# charger_1A.net
KiCad netlist of a schematic drawn in Altium Designer
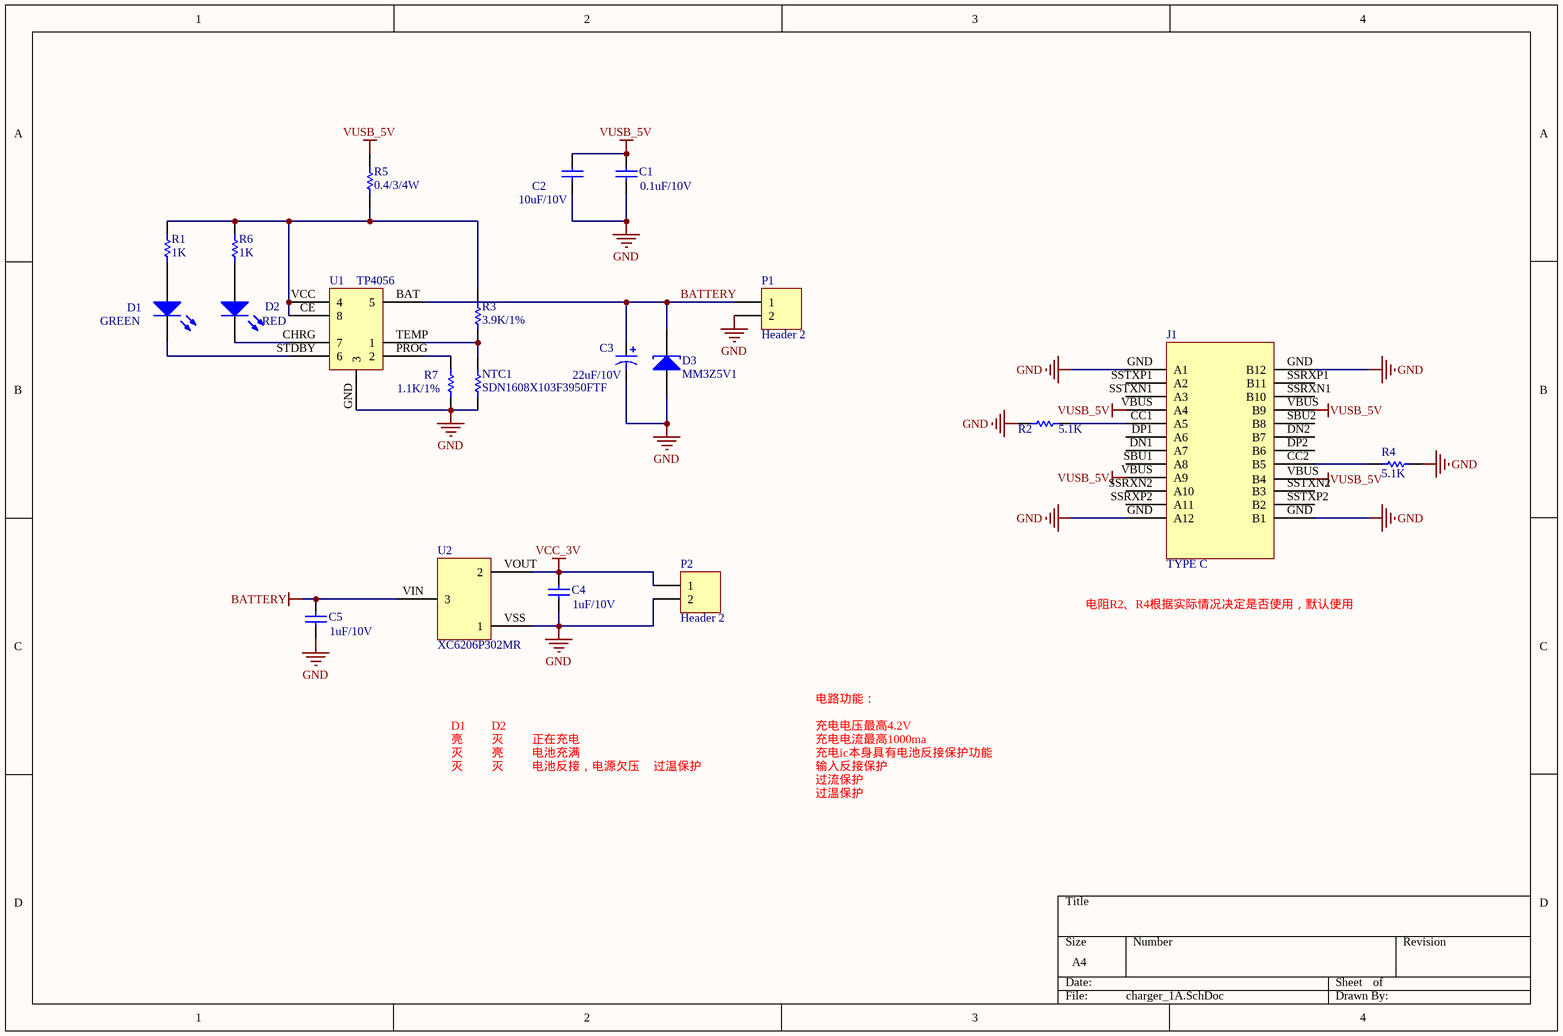
[diagram p0: charger_1A.SchDoc]

(export (version "E")
  (design (tool "Eeschema 10.0.6"))
  (components
    (comp (ref "C1")
      (value "0.1uF/10V")
      (footprint "0603C")
      (description "Capacitor")
      (fields (field (name "PUBLISHER") "Altium Limited"))
      (libsource (lib "Miscellaneous Devices") (part "Cap"))
    )
    (comp (ref "C2")
      (value "10uF/10V")
      (footprint "0603C")
      (description "Capacitor")
      (fields (field (name "PUBLISHER") "Altium Limited"))
      (libsource (lib "Miscellaneous Devices") (part "Cap"))
    )
    (comp (ref "C3")
      (value "22uF/10V")
      (footprint "1210E")
      (description "Polarized Capacitor (Radial)")
      (fields (field (name "PUBLISHER") "Altium Limited"))
      (libsource (lib "Miscellaneous Devices") (part "Cap Pol1"))
    )
    (comp (ref "C4")
      (value "1uF/10V")
      (footprint "0603C")
      (description "Capacitor")
      (fields (field (name "PUBLISHER") "Altium Limited"))
      (libsource (lib "Miscellaneous Devices") (part "Cap"))
    )
    (comp (ref "C5")
      (value "1uF/10V")
      (footprint "0603C")
      (description "Capacitor")
      (fields (field (name "PUBLISHER") "Altium Limited"))
      (libsource (lib "Miscellaneous Devices") (part "Cap"))
    )
    (comp (ref "D1")
      (value "~")
      (footprint "0603LED")
      (description "Typical INFRARED GaAs LED")
      (fields (field (name "PUBLISHER") "GREEN"))
      (libsource (lib "Miscellaneous Devices") (part "LED0"))
    )
    (comp (ref "D2")
      (value "~")
      (footprint "0603LED")
      (description "Typical INFRARED GaAs LED")
      (fields (field (name "PUBLISHER") "RED"))
      (libsource (lib "Miscellaneous Devices") (part "LED0"))
    )
    (comp (ref "D3")
      (value "MM3Z5V1")
      (footprint "SOD323")
      (description "Tunnel Diode - RLC Model")
      (fields (field (name "PUBLISHER") "Altium Limited"))
      (libsource (lib "Miscellaneous Devices") (part "D Tunnel1"))
    )
    (comp (ref "J1") (value "TYPE C") (libsource (lib "CHARGER") (part "TYPE C")))
    (comp (ref "NTC1")
      (value "SDN1608X103F3950FTF")
      (footprint "0603R")
      (description "Semiconductor Resistor")
      (fields (field (name "PUBLISHER") "Altium Limited"))
      (libsource (lib "Miscellaneous Devices") (part "Res Semi"))
    )
    (comp (ref "P1")
      (value "Header 2")
      (footprint "HDR1X2")
      (description "Header, 2-Pin")
      (fields (field (name "PUBLISHER") "Altium Limited"))
      (libsource (lib "Miscellaneous Connectors") (part "Header 2"))
    )
    (comp (ref "P2")
      (value "Header 2")
      (footprint "HDR1X2")
      (description "Header, 2-Pin")
      (fields (field (name "PUBLISHER") "Altium Limited"))
      (libsource (lib "Miscellaneous Connectors") (part "Header 2"))
    )
    (comp (ref "R1")
      (value "1K")
      (footprint "0603R")
      (description "Semiconductor Resistor")
      (fields (field (name "PUBLISHER") "Altium Limited"))
      (libsource (lib "Miscellaneous Devices") (part "Res Semi"))
    )
    (comp (ref "R2")
      (value "5.1K")
      (footprint "0603R")
      (description "Semiconductor Resistor")
      (fields (field (name "PUBLISHER") "Altium Limited"))
      (libsource (lib "Miscellaneous Devices") (part "Res Semi"))
    )
    (comp (ref "R3")
      (value "3.9K/1%")
      (footprint "0603R")
      (description "Semiconductor Resistor")
      (fields (field (name "PUBLISHER") "Altium Limited"))
      (libsource (lib "Miscellaneous Devices") (part "Res Semi"))
    )
    (comp (ref "R4")
      (value "5.1K")
      (footprint "0603R")
      (description "Semiconductor Resistor")
      (fields (field (name "PUBLISHER") "Altium Limited"))
      (libsource (lib "Miscellaneous Devices") (part "Res Semi"))
    )
    (comp (ref "R5")
      (value "0.4/3/4W")
      (footprint "0603R")
      (description "Semiconductor Resistor")
      (fields (field (name "PUBLISHER") "Altium Limited"))
      (libsource (lib "Miscellaneous Devices") (part "Res Semi"))
    )
    (comp (ref "R6")
      (value "1K")
      (footprint "0603R")
      (description "Semiconductor Resistor")
      (fields (field (name "PUBLISHER") "Altium Limited"))
      (libsource (lib "Miscellaneous Devices") (part "Res Semi"))
    )
    (comp (ref "R7")
      (value "1.1K/1%")
      (footprint "0603R")
      (description "Semiconductor Resistor")
      (fields (field (name "PUBLISHER") "Altium Limited"))
      (libsource (lib "Miscellaneous Devices") (part "Res Semi"))
    )
    (comp (ref "U1") (value "TP4056") (libsource (lib "CHARGER") (part "TP4056")))
    (comp (ref "U2") (value "XC6206P302MR") (libsource (lib "CHARGER") (part "XC6206P302MR")))
  )
  (nets
    (net (code "1") (name "BATTERY") (class "Default")
      (node (ref "C3") (pin "1") (pinfunction "1_1") (pintype "passive"))
      (node (ref "C5") (pin "2") (pinfunction "2_2") (pintype "passive"))
      (node (ref "D3") (pin "2") (pinfunction "K_2") (pintype "passive"))
      (node (ref "P1") (pin "1") (pinfunction "1_1") (pintype "passive"))
      (node (ref "U1") (pin "BAT") (pinfunction "5_BAT") (pintype "passive"))
      (node (ref "U2") (pin "VIN") (pinfunction "3_VIN") (pintype "passive"))
    )
    (net (code "2") (name "GND") (class "Default")
      (node (ref "C1") (pin "1") (pinfunction "1_1") (pintype "passive"))
      (node (ref "C2") (pin "1") (pinfunction "1_1") (pintype "passive"))
      (node (ref "C3") (pin "2") (pinfunction "2_2") (pintype "passive"))
      (node (ref "C4") (pin "1") (pinfunction "1_1") (pintype "passive"))
      (node (ref "C5") (pin "1") (pinfunction "1_1") (pintype "passive"))
      (node (ref "D3") (pin "1") (pinfunction "A_1") (pintype "passive"))
      (node (ref "J1") (pin "GND") (pinfunction "B1_GND") (pintype "passive"))
      (node (ref "NTC1") (pin "2") (pinfunction "2_2") (pintype "passive"))
      (node (ref "P1") (pin "2") (pinfunction "2_2") (pintype "passive"))
      (node (ref "P2") (pin "2") (pinfunction "2_2") (pintype "passive"))
      (node (ref "R2") (pin "2") (pinfunction "2_2") (pintype "passive"))
      (node (ref "R4") (pin "2") (pinfunction "2_2") (pintype "passive"))
      (node (ref "R7") (pin "1") (pinfunction "1_1") (pintype "passive"))
      (node (ref "U1") (pin "GND") (pinfunction "3_GND") (pintype "passive"))
      (node (ref "U2") (pin "VSS") (pinfunction "1_VSS") (pintype "passive"))
    )
    (net (code "3") (name "Net-(D1-A)") (class "Default")
      (node (ref "D1") (pin "1") (pinfunction "A_1") (pintype "passive"))
      (node (ref "R1") (pin "1") (pinfunction "1_1") (pintype "passive"))
    )
    (net (code "4") (name "Net-(D1-K)") (class "Default")
      (node (ref "D1") (pin "2") (pinfunction "K_2") (pintype "passive"))
      (node (ref "U1") (pin "STDBY") (pinfunction "6_STDBY") (pintype "passive"))
    )
    (net (code "5") (name "Net-(D2-A)") (class "Default")
      (node (ref "D2") (pin "1") (pinfunction "A_1") (pintype "passive"))
      (node (ref "R6") (pin "1") (pinfunction "1_1") (pintype "passive"))
    )
    (net (code "6") (name "Net-(D2-K)") (class "Default")
      (node (ref "D2") (pin "2") (pinfunction "K_2") (pintype "passive"))
      (node (ref "U1") (pin "CHRG") (pinfunction "7_CHRG") (pintype "passive"))
    )
    (net (code "7") (name "Net-(J1-A5)") (class "Default")
      (node (ref "J1") (pin "CC1") (pinfunction "A5_CC1") (pintype "passive"))
      (node (ref "R2") (pin "1") (pinfunction "1_1") (pintype "passive"))
    )
    (net (code "8") (name "Net-(J1-B5)") (class "Default")
      (node (ref "J1") (pin "CC2") (pinfunction "B5_CC2") (pintype "passive"))
      (node (ref "R4") (pin "1") (pinfunction "1_1") (pintype "passive"))
    )
    (net (code "9") (name "Net-(U1-1)") (class "Default")
      (node (ref "NTC1") (pin "1") (pinfunction "1_1") (pintype "passive"))
      (node (ref "R3") (pin "2") (pinfunction "2_2") (pintype "passive"))
      (node (ref "U1") (pin "TEMP") (pinfunction "1_TEMP") (pintype "passive"))
    )
    (net (code "10") (name "Net-(U1-2)") (class "Default")
      (node (ref "R7") (pin "2") (pinfunction "2_2") (pintype "passive"))
      (node (ref "U1") (pin "PROG") (pinfunction "2_PROG") (pintype "passive"))
    )
    (net (code "11") (name "Net-(U1-4)") (class "Default")
      (node (ref "R1") (pin "2") (pinfunction "2_2") (pintype "passive"))
      (node (ref "R3") (pin "1") (pinfunction "1_1") (pintype "passive"))
      (node (ref "R5") (pin "2") (pinfunction "2_2") (pintype "passive"))
      (node (ref "R6") (pin "2") (pinfunction "2_2") (pintype "passive"))
      (node (ref "U1") (pin "CE") (pinfunction "8_CE") (pintype "passive"))
      (node (ref "U1") (pin "VCC") (pinfunction "4_VCC") (pintype "passive"))
    )
    (net (code "12") (name "VCC_3V") (class "Default")
      (node (ref "C4") (pin "2") (pinfunction "2_2") (pintype "passive"))
      (node (ref "P2") (pin "1") (pinfunction "1_1") (pintype "passive"))
      (node (ref "U2") (pin "VOUT") (pinfunction "2_VOUT") (pintype "passive"))
    )
    (net (code "13") (name "VUSB_5V") (class "Default")
      (node (ref "C1") (pin "2") (pinfunction "2_2") (pintype "passive"))
      (node (ref "C2") (pin "2") (pinfunction "2_2") (pintype "passive"))
      (node (ref "J1") (pin "VBUS") (pinfunction "A4_VBUS") (pintype "passive"))
      (node (ref "R5") (pin "1") (pinfunction "1_1") (pintype "passive"))
    )
    (net (code "14") (name "unconnected-(J1-A2-PadSSTXP1)") (class "Default")
      (node (ref "J1") (pin "SSTXP1") (pinfunction "A2_SSTXP1") (pintype "passive"))
    )
    (net (code "15") (name "unconnected-(J1-A3-PadSSTXN1)") (class "Default")
      (node (ref "J1") (pin "SSTXN1") (pinfunction "A3_SSTXN1") (pintype "passive"))
    )
    (net (code "16") (name "unconnected-(J1-A6-PadDP1)") (class "Default")
      (node (ref "J1") (pin "DP1") (pinfunction "A6_DP1") (pintype "passive"))
    )
    (net (code "17") (name "unconnected-(J1-A7-PadDN1)") (class "Default")
      (node (ref "J1") (pin "DN1") (pinfunction "A7_DN1") (pintype "passive"))
    )
    (net (code "18") (name "unconnected-(J1-A8-PadSBU1)") (class "Default")
      (node (ref "J1") (pin "SBU1") (pinfunction "A8_SBU1") (pintype "passive"))
    )
    (net (code "19") (name "unconnected-(J1-A10-PadSSRXN2)") (class "Default")
      (node (ref "J1") (pin "SSRXN2") (pinfunction "A10_SSRXN2") (pintype "passive"))
    )
    (net (code "20") (name "unconnected-(J1-A11-PadSSRXP2)") (class "Default")
      (node (ref "J1") (pin "SSRXP2") (pinfunction "A11_SSRXP2") (pintype "passive"))
    )
    (net (code "21") (name "unconnected-(J1-B2-PadSSTXP2)") (class "Default")
      (node (ref "J1") (pin "SSTXP2") (pinfunction "B2_SSTXP2") (pintype "passive"))
    )
    (net (code "22") (name "unconnected-(J1-B3-PadSSTXN2)") (class "Default")
      (node (ref "J1") (pin "SSTXN2") (pinfunction "B3_SSTXN2") (pintype "passive"))
    )
    (net (code "23") (name "unconnected-(J1-B6-PadDP2)") (class "Default")
      (node (ref "J1") (pin "DP2") (pinfunction "B6_DP2") (pintype "passive"))
    )
    (net (code "24") (name "unconnected-(J1-B7-PadDN2)") (class "Default")
      (node (ref "J1") (pin "DN2") (pinfunction "B7_DN2") (pintype "passive"))
    )
    (net (code "25") (name "unconnected-(J1-B8-PadSBU2)") (class "Default")
      (node (ref "J1") (pin "SBU2") (pinfunction "B8_SBU2") (pintype "passive"))
    )
    (net (code "26") (name "unconnected-(J1-B10-PadSSRXN1)") (class "Default")
      (node (ref "J1") (pin "SSRXN1") (pinfunction "B10_SSRXN1") (pintype "passive"))
    )
    (net (code "27") (name "unconnected-(J1-B11-PadSSRXP1)") (class "Default")
      (node (ref "J1") (pin "SSRXP1") (pinfunction "B11_SSRXP1") (pintype "passive"))
    )
  )
)
